# asdf.net
KiCad netlist of a schematic drawn in EAGLE
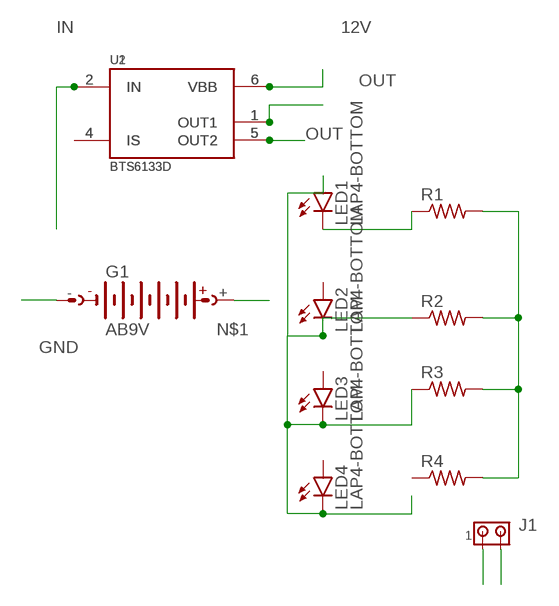
[diagram p0: schematic, sheet 1]

(export (version "E")
  (design (tool "Eeschema 10.0.6"))
  (components
    (comp (ref "G1")
      (value "AB9V")
      (footprint "eagle-import:AB9V")
      (libsource (lib "eagle-import") (part "AB9V"))
    )
    (comp (ref "J1")
      (value "MTA02-100")
      (footprint "eagle-import:10X02MTA")
      (libsource (lib "eagle-import") (part "MTA02-100"))
    )
    (comp (ref "LED1")
      (value "LAP4-BOTTOM")
      (footprint "eagle-import:P47F-BOTTOM")
      (libsource (lib "eagle-import") (part "P4-BOTTOMLA"))
    )
    (comp (ref "LED2")
      (value "LAP4-BOTTOM")
      (footprint "eagle-import:P47F-BOTTOM")
      (libsource (lib "eagle-import") (part "P4-BOTTOMLA"))
    )
    (comp (ref "LED3")
      (value "LAP4-BOTTOM")
      (footprint "eagle-import:P47F-BOTTOM")
      (libsource (lib "eagle-import") (part "P4-BOTTOMLA"))
    )
    (comp (ref "LED4")
      (value "LAP4-BOTTOM")
      (footprint "eagle-import:P47F-BOTTOM")
      (libsource (lib "eagle-import") (part "P4-BOTTOMLA"))
    )
    (comp (ref "R1")
      (value "R-US_0207/10")
      (footprint "eagle-import:0207_10")
      (libsource (lib "eagle-import") (part "R-US_0207/10"))
    )
    (comp (ref "R2")
      (value "R-US_0207/10")
      (footprint "eagle-import:0207_10")
      (libsource (lib "eagle-import") (part "R-US_0207/10"))
    )
    (comp (ref "R3")
      (value "R-US_0207/10")
      (footprint "eagle-import:0207_10")
      (libsource (lib "eagle-import") (part "R-US_0207/10"))
    )
    (comp (ref "R4")
      (value "R-US_0207/10")
      (footprint "eagle-import:0207_10")
      (libsource (lib "eagle-import") (part "R-US_0207/10"))
    )
    (comp (ref "U1")
      (value "BTS6133D")
      (footprint "eagle-import:TO114P998X235-6_5N-V")
      (libsource (lib "eagle-import") (part "BTS6133D"))
    )
    (comp (ref "U2")
      (value "BTS6133D")
      (footprint "eagle-import:TO114P998X235-6_5N-V")
      (libsource (lib "eagle-import") (part "BTS6133D"))
    )
  )
  (nets
    (net (code "1") (name "/12V") (class "Default")
      (node (ref "U1") (pin "6") (pinfunction "VBB_6") (pintype "power_in"))
      (node (ref "U2") (pin "6") (pinfunction "VBB_6") (pintype "power_in"))
    )
    (net (code "2") (name "/GND") (class "Default")
      (node (ref "G1") (pin "-") (pinfunction "-_-") (pintype "passive"))
    )
    (net (code "3") (name "/IN") (class "Default")
      (node (ref "U1") (pin "2") (pinfunction "IN_2") (pintype "input"))
      (node (ref "U2") (pin "2") (pinfunction "IN_2") (pintype "input"))
    )
    (net (code "4") (name "/N$1") (class "Default")
      (node (ref "G1") (pin "+") (pinfunction "+_+") (pintype "passive"))
    )
    (net (code "5") (name "/OUT") (class "Default")
      (node (ref "U1") (pin "1") (pinfunction "OUT1_1") (pintype "output"))
      (node (ref "U1") (pin "5") (pinfunction "OUT2_5") (pintype "output"))
      (node (ref "U2") (pin "1") (pinfunction "OUT1_1") (pintype "output"))
      (node (ref "U2") (pin "5") (pinfunction "OUT2_5") (pintype "output"))
    )
    (net (code "6") (name "Net-(LED1-PadA)") (class "Default")
      (node (ref "LED1") (pin "A") (pinfunction "A_A") (pintype "passive"))
      (node (ref "LED2") (pin "C") (pinfunction "C_C") (pintype "passive"))
      (node (ref "LED3") (pin "C") (pinfunction "C_C") (pintype "passive"))
      (node (ref "LED4") (pin "C") (pinfunction "C_C") (pintype "passive"))
      (node (ref "R2") (pin "1") (pinfunction "1_1") (pintype "passive"))
      (node (ref "R3") (pin "1") (pinfunction "1_1") (pintype "passive"))
    )
    (net (code "7") (name "Net-(LED1-PadC)") (class "Default")
      (node (ref "LED1") (pin "C") (pinfunction "C_C") (pintype "passive"))
      (node (ref "R1") (pin "1") (pinfunction "1_1") (pintype "passive"))
    )
    (net (code "8") (name "Net-(R1-Pad2)") (class "Default")
      (node (ref "R1") (pin "2") (pinfunction "2_2") (pintype "passive"))
      (node (ref "R2") (pin "2") (pinfunction "2_2") (pintype "passive"))
      (node (ref "R3") (pin "2") (pinfunction "2_2") (pintype "passive"))
      (node (ref "R4") (pin "2") (pinfunction "2_2") (pintype "passive"))
    )
    (net (code "9") (name "Net-(U1-IS)") (class "Default")
      (node (ref "U1") (pin "4") (pinfunction "IS_4") (pintype "output"))
      (node (ref "U2") (pin "4") (pinfunction "IS_4") (pintype "output"))
    )
    (net (code "10") (name "unconnected-(J1-Pad1)") (class "Default")
      (node (ref "J1") (pin "1") (pinfunction "1_1") (pintype "passive"))
    )
    (net (code "11") (name "unconnected-(J1-Pad2)") (class "Default")
      (node (ref "J1") (pin "2") (pinfunction "2_2") (pintype "passive"))
    )
    (net (code "12") (name "unconnected-(LED2-PadA)") (class "Default")
      (node (ref "LED2") (pin "A") (pinfunction "A_A") (pintype "passive"))
    )
    (net (code "13") (name "unconnected-(LED3-PadA)") (class "Default")
      (node (ref "LED3") (pin "A") (pinfunction "A_A") (pintype "passive"))
    )
    (net (code "14") (name "unconnected-(LED4-PadA)") (class "Default")
      (node (ref "LED4") (pin "A") (pinfunction "A_A") (pintype "passive"))
    )
    (net (code "15") (name "unconnected-(R4-Pad1)") (class "Default")
      (node (ref "R4") (pin "1") (pinfunction "1_1") (pintype "passive"))
    )
  )
)
